# Motor.net
KiCad netlist of a schematic drawn in Altium Designer
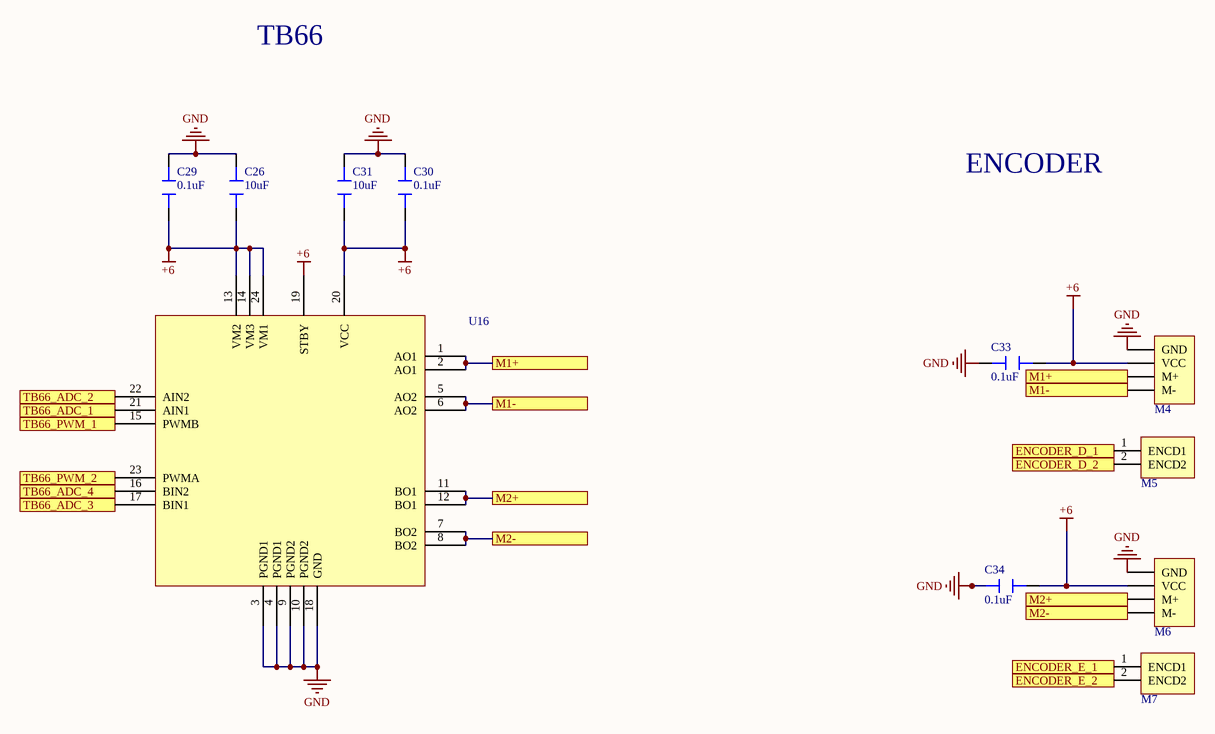
[diagram p0: Motor.SchDoc]

(export (version "E")
  (design (tool "Eeschema 10.0.6"))
  (components
    (comp (ref "C26")
      (value "10uF")
      (footprint "CAPACITOR 0603")
      (description "Capacitores de cerâmica multicamada MLCC - SMD/SMT 0603 16Vdc 10uF X6S 20%")
      (fields
        (field (name "MANUFACTURER") "Murata")
        (field (name "MANUFACTURER PART NUMBER") "GRT188C81C106ME13D")
      )
      (libsource (lib "BiricuticoBonito") (part "Capacitor 10uF 0603"))
    )
    (comp (ref "C29")
      (value "0.1uF")
      (footprint "CAPACITOR 0805")
      (description "Multilayer Ceramic Capacitors MLCC - SMD/SMT .1uF 50volts 10%")
      (fields
        (field (name "MANUFACTURER") "Vishay Vitramon")
        (field (name "MANUFACTURER PART NUMBER") "VJ0805Y104KXAAT")
      )
      (libsource (lib "BiricuticoBonito") (part "Capacitor  0.1uF 0805"))
    )
    (comp (ref "C30")
      (value "0.1uF")
      (footprint "CAPACITOR 0805")
      (description "Multilayer Ceramic Capacitors MLCC - SMD/SMT .1uF 50volts 10%")
      (fields
        (field (name "MANUFACTURER") "Vishay Vitramon")
        (field (name "MANUFACTURER PART NUMBER") "VJ0805Y104KXAAT")
      )
      (libsource (lib "BiricuticoBonito") (part "Capacitor  0.1uF 0805"))
    )
    (comp (ref "C31")
      (value "10uF")
      (footprint "CAPACITOR 0603")
      (description "Capacitores de cerâmica multicamada MLCC - SMD/SMT 0603 16Vdc 10uF X6S 20%")
      (fields
        (field (name "MANUFACTURER") "Murata")
        (field (name "MANUFACTURER PART NUMBER") "GRT188C81C106ME13D")
      )
      (libsource (lib "BiricuticoBonito") (part "Capacitor 10uF 0603"))
    )
    (comp (ref "C33")
      (value "0.1uF")
      (footprint "CAPACITOR 0805")
      (description "Multilayer Ceramic Capacitors MLCC - SMD/SMT .1uF 50volts 10%")
      (fields
        (field (name "MANUFACTURER") "Vishay Vitramon")
        (field (name "MANUFACTURER PART NUMBER") "VJ0805Y104KXAAT")
      )
      (libsource (lib "BiricuticoBonito") (part "Capacitor  0.1uF 0805"))
    )
    (comp (ref "C34")
      (value "0.1uF")
      (footprint "CAPACITOR 0805")
      (description "Multilayer Ceramic Capacitors MLCC - SMD/SMT .1uF 50volts 10%")
      (fields
        (field (name "MANUFACTURER") "Vishay Vitramon")
        (field (name "MANUFACTURER PART NUMBER") "VJ0805Y104KXAAT")
      )
      (libsource (lib "BiricuticoBonito") (part "Capacitor  0.1uF 0805"))
    )
    (comp (ref "M4")
      (value "Headers (1x4)")
      (footprint "HDR1X4")
      (description "Header, 4-Pin")
      (fields (field (name "PUBLISHER") "Altium Limited"))
      (libsource (lib "BiricuticoBonito") (part "Headers (1x4)"))
    )
    (comp (ref "M5")
      (value "Headers (1x2)ENC")
      (footprint "HDR1X2")
      (description "Headers & Wire Housings HDR STRT SINGLE 2P")
      (fields (field (name "MANUFACTURER") "Molex") (field (name "MANUFACTURER PART NUMBER") "90136-1202"))
      (libsource (lib "BiricuticoBonito") (part "Headers (1x2)ENC"))
    )
    (comp (ref "M6")
      (value "Headers (1x4)")
      (footprint "HDR1X4")
      (description "Header, 4-Pin")
      (fields (field (name "PUBLISHER") "Altium Limited"))
      (libsource (lib "BiricuticoBonito") (part "Headers (1x4)"))
    )
    (comp (ref "M7")
      (value "Headers (1x2)ENC")
      (footprint "HDR1X2")
      (description "Headers & Wire Housings HDR STRT SINGLE 2P")
      (fields (field (name "MANUFACTURER") "Molex") (field (name "MANUFACTURER PART NUMBER") "90136-1202"))
      (libsource (lib "BiricuticoBonito") (part "Headers (1x2)ENC"))
    )
    (comp (ref "U16")
      (value "Driver TB6612FNG")
      (footprint "SOP65P760X160-24N")
      (description "DC Motor Driver 3V 24-Pin SSOP T/R")
      (fields
        (field (name "MANUFACTURER") "Toshiba")
        (field (name "MANUFACTURER PART NUMBER") "TB6612FNG,C,8,EL")
      )
      (libsource (lib "BiricuticoBonito") (part "Driver TB6612FNG"))
    )
  )
  (nets
    (net (code "1") (name "+6") (class "Default")
      (node (ref "C26") (pin "1") (pinfunction "33_1") (pintype "passive"))
      (node (ref "C29") (pin "1") (pinfunction "33_1") (pintype "passive"))
      (node (ref "C30") (pin "1") (pinfunction "33_1") (pintype "passive"))
      (node (ref "C31") (pin "1") (pinfunction "33_1") (pintype "passive"))
      (node (ref "C33") (pin "1") (pinfunction "33_1") (pintype "passive"))
      (node (ref "C34") (pin "2") (pinfunction "34_2") (pintype "passive"))
      (node (ref "M4") (pin "2") (pinfunction "VCC_2") (pintype "passive"))
      (node (ref "M6") (pin "2") (pinfunction "VCC_2") (pintype "passive"))
      (node (ref "U16") (pin "13") (pinfunction "VM2_13") (pintype "passive"))
      (node (ref "U16") (pin "14") (pinfunction "VM3_14") (pintype "passive"))
      (node (ref "U16") (pin "19") (pinfunction "STBY_19") (pintype "passive"))
      (node (ref "U16") (pin "20") (pinfunction "VCC_20") (pintype "passive"))
      (node (ref "U16") (pin "24") (pinfunction "VM1_24") (pintype "passive"))
    )
    (net (code "2") (name "/ENCODER_D_1") (class "Default")
      (node (ref "M5") (pin "1") (pinfunction "ENCD1_1") (pintype "passive"))
    )
    (net (code "3") (name "/ENCODER_D_2") (class "Default")
      (node (ref "M5") (pin "2") (pinfunction "ENCD2_2") (pintype "passive"))
    )
    (net (code "4") (name "/ENCODER_E_1") (class "Default")
      (node (ref "M7") (pin "1") (pinfunction "ENCD1_1") (pintype "passive"))
    )
    (net (code "5") (name "/ENCODER_E_2") (class "Default")
      (node (ref "M7") (pin "2") (pinfunction "ENCD2_2") (pintype "passive"))
    )
    (net (code "6") (name "/M1+") (class "Default")
      (node (ref "M4") (pin "3") (pinfunction "M+_3") (pintype "passive"))
      (node (ref "U16") (pin "1") (pinfunction "AO1_1") (pintype "passive"))
      (node (ref "U16") (pin "2") (pinfunction "AO1_2") (pintype "passive"))
    )
    (net (code "7") (name "/M1-") (class "Default")
      (node (ref "M4") (pin "4") (pinfunction "M-_4") (pintype "passive"))
      (node (ref "U16") (pin "5") (pinfunction "AO2_5") (pintype "passive"))
      (node (ref "U16") (pin "6") (pinfunction "AO2_6") (pintype "passive"))
    )
    (net (code "8") (name "/M2+") (class "Default")
      (node (ref "M6") (pin "3") (pinfunction "M+_3") (pintype "passive"))
      (node (ref "U16") (pin "11") (pinfunction "BO1_11") (pintype "passive"))
      (node (ref "U16") (pin "12") (pinfunction "BO1_12") (pintype "passive"))
    )
    (net (code "9") (name "/M2-") (class "Default")
      (node (ref "M6") (pin "4") (pinfunction "M-_4") (pintype "passive"))
      (node (ref "U16") (pin "7") (pinfunction "BO2_7") (pintype "passive"))
      (node (ref "U16") (pin "8") (pinfunction "BO2_8") (pintype "passive"))
    )
    (net (code "10") (name "/TB66_ADC_1") (class "Default")
      (node (ref "U16") (pin "21") (pinfunction "AIN1_21") (pintype "passive"))
    )
    (net (code "11") (name "/TB66_ADC_2") (class "Default")
      (node (ref "U16") (pin "22") (pinfunction "AIN2_22") (pintype "passive"))
    )
    (net (code "12") (name "/TB66_ADC_3") (class "Default")
      (node (ref "U16") (pin "17") (pinfunction "BIN1_17") (pintype "passive"))
    )
    (net (code "13") (name "/TB66_ADC_4") (class "Default")
      (node (ref "U16") (pin "16") (pinfunction "BIN2_16") (pintype "passive"))
    )
    (net (code "14") (name "/TB66_PWM_1") (class "Default")
      (node (ref "U16") (pin "15") (pinfunction "PWMB_15") (pintype "passive"))
    )
    (net (code "15") (name "/TB66_PWM_2") (class "Default")
      (node (ref "U16") (pin "23") (pinfunction "PWMA_23") (pintype "passive"))
    )
    (net (code "16") (name "GND") (class "Default")
      (node (ref "C26") (pin "2") (pinfunction "34_2") (pintype "passive"))
      (node (ref "C29") (pin "2") (pinfunction "34_2") (pintype "passive"))
      (node (ref "C30") (pin "2") (pinfunction "34_2") (pintype "passive"))
      (node (ref "C31") (pin "2") (pinfunction "34_2") (pintype "passive"))
      (node (ref "C33") (pin "2") (pinfunction "34_2") (pintype "passive"))
      (node (ref "C34") (pin "1") (pinfunction "33_1") (pintype "passive"))
      (node (ref "M4") (pin "1") (pinfunction "GND_1") (pintype "passive"))
      (node (ref "M6") (pin "1") (pinfunction "GND_1") (pintype "passive"))
      (node (ref "U16") (pin "10") (pinfunction "PGND2_10") (pintype "passive"))
      (node (ref "U16") (pin "18") (pinfunction "GND_18") (pintype "passive"))
      (node (ref "U16") (pin "3") (pinfunction "PGND1_3") (pintype "passive"))
      (node (ref "U16") (pin "4") (pinfunction "PGND1_4") (pintype "passive"))
      (node (ref "U16") (pin "9") (pinfunction "PGND2_9") (pintype "passive"))
    )
  )
)
